# lux.net
KiCad netlist of a schematic drawn in EAGLE
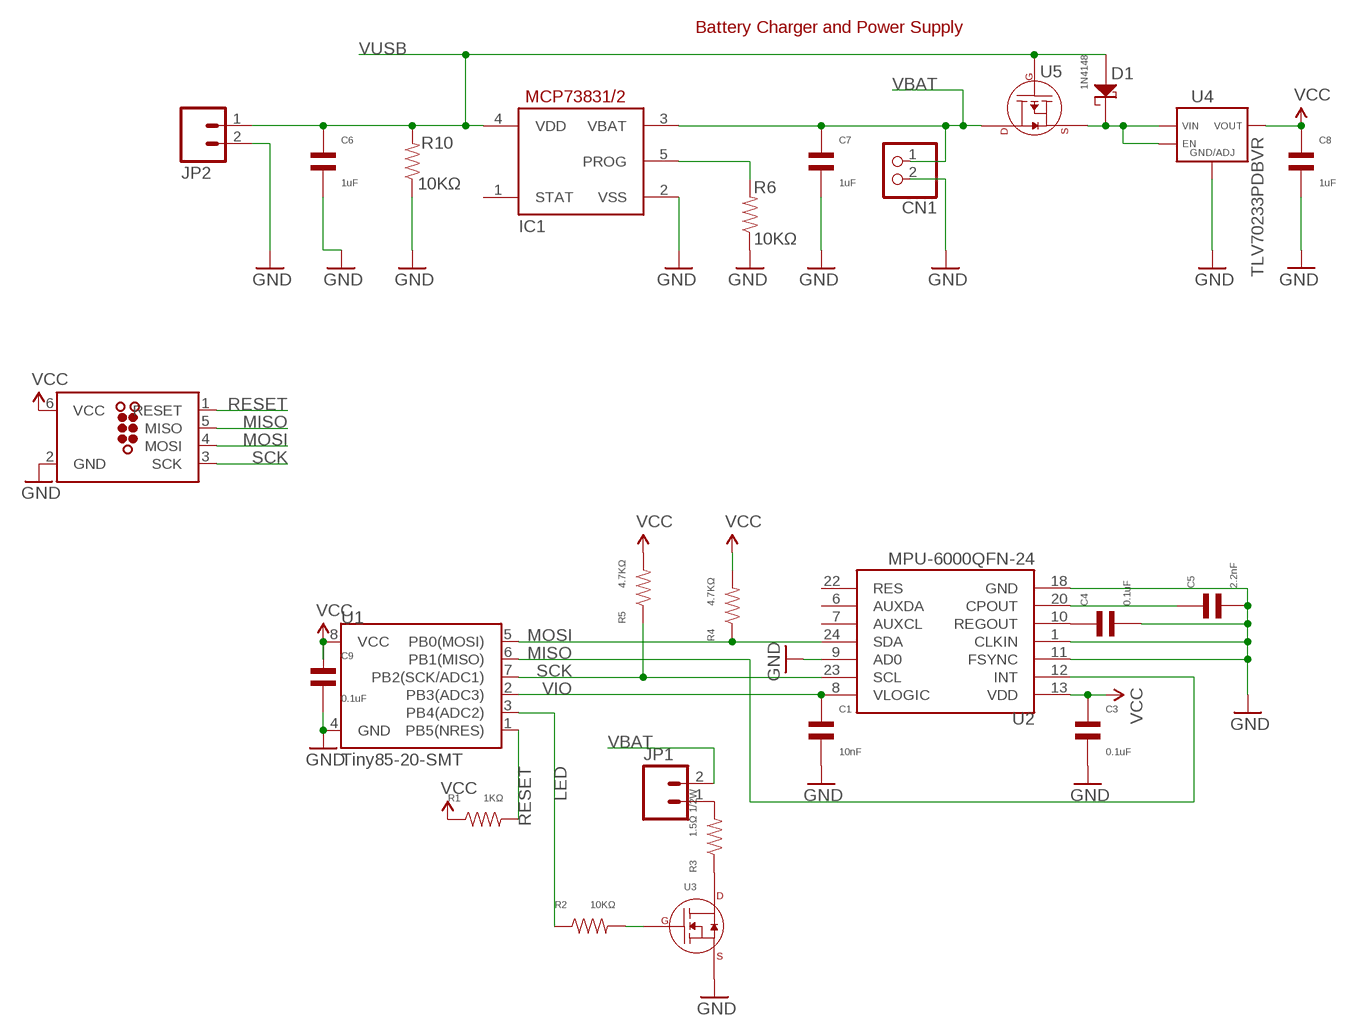
[diagram p0: schematic, sheet 1]

(export (version "E")
  (design (tool "Eeschema 10.0.6"))
  (components
    (comp (ref "C1")
      (value "10nF")
      (footprint "eagle-import:C0805")
      (libsource (lib "eagle-import") (part "CAPACITOR_NP_0805"))
    )
    (comp (ref "C3")
      (value "0.1uF")
      (footprint "eagle-import:C0805")
      (libsource (lib "eagle-import") (part "CAPACITOR_NP_0805"))
    )
    (comp (ref "C4")
      (value "0.1uF")
      (footprint "eagle-import:C0805")
      (libsource (lib "eagle-import") (part "CAPACITOR_NP_0805"))
    )
    (comp (ref "C5")
      (value "2.2nF")
      (footprint "eagle-import:C0805")
      (libsource (lib "eagle-import") (part "CAPACITOR_NP_0805"))
    )
    (comp (ref "C6")
      (value "1uF")
      (footprint "eagle-import:C0805")
      (libsource (lib "eagle-import") (part "CAPACITOR_NP_0805"))
    )
    (comp (ref "C7")
      (value "1uF")
      (footprint "eagle-import:C0805")
      (libsource (lib "eagle-import") (part "CAPACITOR_NP_0805"))
    )
    (comp (ref "C8")
      (value "1uF")
      (footprint "eagle-import:C0805")
      (libsource (lib "eagle-import") (part "CAPACITOR_NP_0805"))
    )
    (comp (ref "C9")
      (value "0.1uF")
      (footprint "eagle-import:C0805")
      (libsource (lib "eagle-import") (part "CAPACITOR_NP_0805"))
    )
    (comp (ref "CN1")
      (value "JST_2PIN-SMT-RA")
      (footprint "eagle-import:JST-PH-2-SMT-RA")
      (libsource (lib "eagle-import") (part "JST_2PIN-SMT-RA"))
    )
    (comp (ref "D1")
      (value "1N4148")
      (footprint "eagle-import:SOD-123")
      (libsource (lib "eagle-import") (part "DIODE_SOD-123"))
    )
    (comp (ref "IC1")
      (value "MCP73831/OT")
      (footprint "eagle-import:SOT23-5L")
      (libsource (lib "eagle-import") (part "MCP73831/OT"))
    )
    (comp (ref "J1")
      (value "TC2030-MCP-NLFIX")
      (footprint "eagle-import:TC2030-MCP-NL")
      (libsource (lib "eagle-import") (part "TC2030-MCP-NLFIX"))
    )
    (comp (ref "JP1")
      (value "M02PTH")
      (footprint "eagle-import:1X02")
      (libsource (lib "eagle-import") (part "M02PTH"))
    )
    (comp (ref "JP2")
      (value "M02PTH")
      (footprint "eagle-import:1X02")
      (libsource (lib "eagle-import") (part "M02PTH"))
    )
    (comp (ref "R1")
      (value "1KΩ")
      (footprint "eagle-import:R0805")
      (libsource (lib "eagle-import") (part "RESISTOR_0805"))
    )
    (comp (ref "R2")
      (value "10KΩ")
      (footprint "eagle-import:R0805")
      (libsource (lib "eagle-import") (part "RESISTOR_0805"))
    )
    (comp (ref "R3")
      (value "1.5Ω 1/2W")
      (footprint "eagle-import:R0805")
      (libsource (lib "eagle-import") (part "RESISTOR_0805"))
    )
    (comp (ref "R4")
      (value "4.7KΩ")
      (footprint "eagle-import:R0805")
      (libsource (lib "eagle-import") (part "RESISTOR_0805"))
    )
    (comp (ref "R5")
      (value "4.7KΩ")
      (footprint "eagle-import:R0805")
      (libsource (lib "eagle-import") (part "RESISTOR_0805"))
    )
    (comp (ref "R6")
      (value "10KΩ")
      (footprint "eagle-import:R0805")
      (libsource (lib "eagle-import") (part "RESISTOR_0805"))
    )
    (comp (ref "R10")
      (value "10KΩ")
      (footprint "eagle-import:R0805")
      (libsource (lib "eagle-import") (part "RESISTOR_0805"))
    )
    (comp (ref "U1")
      (value "Tiny85-20-SMT")
      (footprint "eagle-import:SO08-EIAJ")
      (libsource (lib "eagle-import") (part "ATTINY45TINY85-20-SMT"))
    )
    (comp (ref "U2")
      (value "MPU-6000QFN-24")
      (footprint "eagle-import:QFN-24-TESTING")
      (libsource (lib "eagle-import") (part "MPU-6000QFN-24"))
    )
    (comp (ref "U3")
      (value "N-CHANNEL_FET_SOT-23-3")
      (footprint "eagle-import:SOT-23-3")
      (libsource (lib "eagle-import") (part "N-CHANNEL_FET_SOT-23-3"))
    )
    (comp (ref "U4")
      (value "TLV70233PDBVR")
      (footprint "eagle-import:SOT-23-5")
      (libsource (lib "eagle-import") (part "TLV70233PDBVR"))
    )
    (comp (ref "U5")
      (value "P-CHANNEL_FET_SOT-23-3")
      (footprint "eagle-import:SOT-23-3")
      (libsource (lib "eagle-import") (part "P-CHANNEL_FET_SOT-23-3"))
    )
  )
  (nets
    (net (code "1") (name "/LED") (class "Default")
      (node (ref "R2") (pin "P$1") (pinfunction "P$1_P$1") (pintype "passive"))
      (node (ref "U1") (pin "3") (pinfunction "PB4(ADC2)_3") (pintype "bidirectional"))
    )
    (net (code "2") (name "/MISO") (class "Default")
      (node (ref "J1") (pin "5") (pinfunction "MISO_5") (pintype "bidirectional"))
      (node (ref "U1") (pin "6") (pinfunction "PB1(MISO)_6") (pintype "bidirectional"))
      (node (ref "U2") (pin "12") (pinfunction "INT_12") (pintype "bidirectional"))
    )
    (net (code "3") (name "/MOSI") (class "Default")
      (node (ref "J1") (pin "4") (pinfunction "MOSI_4") (pintype "bidirectional"))
      (node (ref "R4") (pin "P$1") (pinfunction "P$1_P$1") (pintype "passive"))
      (node (ref "U1") (pin "5") (pinfunction "PB0(MOSI)_5") (pintype "bidirectional"))
      (node (ref "U2") (pin "24") (pinfunction "SDA_24") (pintype "bidirectional"))
    )
    (net (code "4") (name "/RESET") (class "Default")
      (node (ref "J1") (pin "1") (pinfunction "RESET_1") (pintype "bidirectional"))
      (node (ref "R1") (pin "P$2") (pinfunction "P$2_P$2") (pintype "passive"))
      (node (ref "U1") (pin "1") (pinfunction "PB5(NRES)_1") (pintype "bidirectional"))
    )
    (net (code "5") (name "/SCK") (class "Default")
      (node (ref "J1") (pin "3") (pinfunction "SCK_3") (pintype "bidirectional"))
      (node (ref "R5") (pin "P$1") (pinfunction "P$1_P$1") (pintype "passive"))
      (node (ref "U1") (pin "7") (pinfunction "PB2(SCK/ADC1)_7") (pintype "bidirectional"))
      (node (ref "U2") (pin "23") (pinfunction "SCL_23") (pintype "bidirectional"))
    )
    (net (code "6") (name "/VBAT") (class "Default")
      (node (ref "C7") (pin "P$1") (pinfunction "P$1_P$1") (pintype "passive"))
      (node (ref "CN1") (pin "1") (pinfunction "2_1") (pintype "passive"))
      (node (ref "IC1") (pin "3") (pinfunction "VBAT_3") (pintype "bidirectional"))
      (node (ref "JP1") (pin "2") (pinfunction "2_2") (pintype "passive"))
      (node (ref "U5") (pin "P$3") (pinfunction "DRAIN_P$3") (pintype "bidirectional"))
    )
    (net (code "7") (name "/VIO") (class "Default")
      (node (ref "C1") (pin "P$1") (pinfunction "P$1_P$1") (pintype "passive"))
      (node (ref "U1") (pin "2") (pinfunction "PB3(ADC3)_2") (pintype "bidirectional"))
      (node (ref "U2") (pin "8") (pinfunction "VLOGIC_8") (pintype "bidirectional"))
    )
    (net (code "8") (name "/VUSB") (class "Default")
      (node (ref "C6") (pin "P$1") (pinfunction "P$1_P$1") (pintype "passive"))
      (node (ref "D1") (pin "ANODE") (pinfunction "ANODE_ANODE") (pintype "bidirectional"))
      (node (ref "IC1") (pin "4") (pinfunction "VDD_4") (pintype "power_in"))
      (node (ref "JP2") (pin "1") (pinfunction "1_1") (pintype "passive"))
      (node (ref "R10") (pin "P$2") (pinfunction "P$2_P$2") (pintype "passive"))
      (node (ref "U5") (pin "P$1") (pinfunction "GATE_P$1") (pintype "bidirectional"))
    )
    (net (code "9") (name "GND") (class "Default")
      (node (ref "C1") (pin "P$2") (pinfunction "P$2_P$2") (pintype "passive"))
      (node (ref "C3") (pin "P$2") (pinfunction "P$2_P$2") (pintype "passive"))
      (node (ref "C4") (pin "P$2") (pinfunction "P$2_P$2") (pintype "passive"))
      (node (ref "C5") (pin "P$2") (pinfunction "P$2_P$2") (pintype "passive"))
      (node (ref "C6") (pin "P$2") (pinfunction "P$2_P$2") (pintype "passive"))
      (node (ref "C7") (pin "P$2") (pinfunction "P$2_P$2") (pintype "passive"))
      (node (ref "C8") (pin "P$2") (pinfunction "P$2_P$2") (pintype "passive"))
      (node (ref "C9") (pin "P$2") (pinfunction "P$2_P$2") (pintype "passive"))
      (node (ref "CN1") (pin "2") (pinfunction "1_2") (pintype "passive"))
      (node (ref "IC1") (pin "2") (pinfunction "VSS_2") (pintype "power_in"))
      (node (ref "J1") (pin "2") (pinfunction "GND_2") (pintype "power_in"))
      (node (ref "JP2") (pin "2") (pinfunction "2_2") (pintype "passive"))
      (node (ref "R10") (pin "P$1") (pinfunction "P$1_P$1") (pintype "passive"))
      (node (ref "R6") (pin "P$1") (pinfunction "P$1_P$1") (pintype "passive"))
      (node (ref "U1") (pin "4") (pinfunction "GND_4") (pintype "bidirectional"))
      (node (ref "U2") (pin "1") (pinfunction "CLKIN_1") (pintype "bidirectional"))
      (node (ref "U2") (pin "11") (pinfunction "FSYNC_11") (pintype "bidirectional"))
      (node (ref "U2") (pin "18") (pinfunction "GND_18") (pintype "bidirectional"))
      (node (ref "U2") (pin "9") (pinfunction "AD0_9") (pintype "bidirectional"))
      (node (ref "U3") (pin "P$2") (pinfunction "SOURCE_P$2") (pintype "bidirectional"))
      (node (ref "U4") (pin "P$2") (pinfunction "GND/ADJ_P$2") (pintype "bidirectional"))
    )
    (net (code "10") (name "Net-(IC1-PROG)") (class "Default")
      (node (ref "IC1") (pin "5") (pinfunction "PROG_5") (pintype "input"))
      (node (ref "R6") (pin "P$2") (pinfunction "P$2_P$2") (pintype "passive"))
    )
    (net (code "11") (name "Net-(JP1-Pad1)") (class "Default")
      (node (ref "JP1") (pin "1") (pinfunction "1_1") (pintype "passive"))
      (node (ref "R3") (pin "P$2") (pinfunction "P$2_P$2") (pintype "passive"))
    )
    (net (code "12") (name "Net-(U2-CPOUT)") (class "Default")
      (node (ref "C5") (pin "P$1") (pinfunction "P$1_P$1") (pintype "passive"))
      (node (ref "U2") (pin "20") (pinfunction "CPOUT_20") (pintype "bidirectional"))
    )
    (net (code "13") (name "Net-(U2-REGOUT)") (class "Default")
      (node (ref "C4") (pin "P$1") (pinfunction "P$1_P$1") (pintype "passive"))
      (node (ref "U2") (pin "10") (pinfunction "REGOUT_10") (pintype "bidirectional"))
    )
    (net (code "14") (name "Net-(U3-DRAIN)") (class "Default")
      (node (ref "R3") (pin "P$1") (pinfunction "P$1_P$1") (pintype "passive"))
      (node (ref "U3") (pin "P$3") (pinfunction "DRAIN_P$3") (pintype "bidirectional"))
    )
    (net (code "15") (name "Net-(U3-GATE)") (class "Default")
      (node (ref "R2") (pin "P$2") (pinfunction "P$2_P$2") (pintype "passive"))
      (node (ref "U3") (pin "P$1") (pinfunction "GATE_P$1") (pintype "bidirectional"))
    )
    (net (code "16") (name "Net-(U4-EN)") (class "Default")
      (node (ref "D1") (pin "CATHODE") (pinfunction "CATHODE_CATHODE") (pintype "bidirectional"))
      (node (ref "U4") (pin "P$1") (pinfunction "VIN_P$1") (pintype "bidirectional"))
      (node (ref "U4") (pin "P$3") (pinfunction "EN_P$3") (pintype "bidirectional"))
      (node (ref "U5") (pin "P$2") (pinfunction "SOURCE_P$2") (pintype "bidirectional"))
    )
    (net (code "17") (name "VCC") (class "Default")
      (node (ref "C3") (pin "P$1") (pinfunction "P$1_P$1") (pintype "passive"))
      (node (ref "C8") (pin "P$1") (pinfunction "P$1_P$1") (pintype "passive"))
      (node (ref "C9") (pin "P$1") (pinfunction "P$1_P$1") (pintype "passive"))
      (node (ref "J1") (pin "6") (pinfunction "VCC_6") (pintype "power_in"))
      (node (ref "R1") (pin "P$1") (pinfunction "P$1_P$1") (pintype "passive"))
      (node (ref "R4") (pin "P$2") (pinfunction "P$2_P$2") (pintype "passive"))
      (node (ref "R5") (pin "P$2") (pinfunction "P$2_P$2") (pintype "passive"))
      (node (ref "U1") (pin "8") (pinfunction "VCC_8") (pintype "bidirectional"))
      (node (ref "U2") (pin "13") (pinfunction "VDD_13") (pintype "bidirectional"))
      (node (ref "U4") (pin "P$5") (pinfunction "VOUT_P$5") (pintype "bidirectional"))
    )
    (net (code "18") (name "unconnected-(IC1-STAT-Pad1)") (class "Default")
      (node (ref "IC1") (pin "1") (pinfunction "STAT_1") (pintype "output"))
    )
    (net (code "19") (name "unconnected-(U2-AUXCL-Pad7)") (class "Default")
      (node (ref "U2") (pin "7") (pinfunction "AUXCL_7") (pintype "bidirectional"))
    )
    (net (code "20") (name "unconnected-(U2-AUXDA-Pad6)") (class "Default")
      (node (ref "U2") (pin "6") (pinfunction "AUXDA_6") (pintype "bidirectional"))
    )
    (net (code "21") (name "unconnected-(U2-RES-Pad22)") (class "Default")
      (node (ref "U2") (pin "22") (pinfunction "RES_22") (pintype "bidirectional"))
    )
  )
)
